# peaks_v30.net
KiCad netlist of a schematic drawn in EAGLE
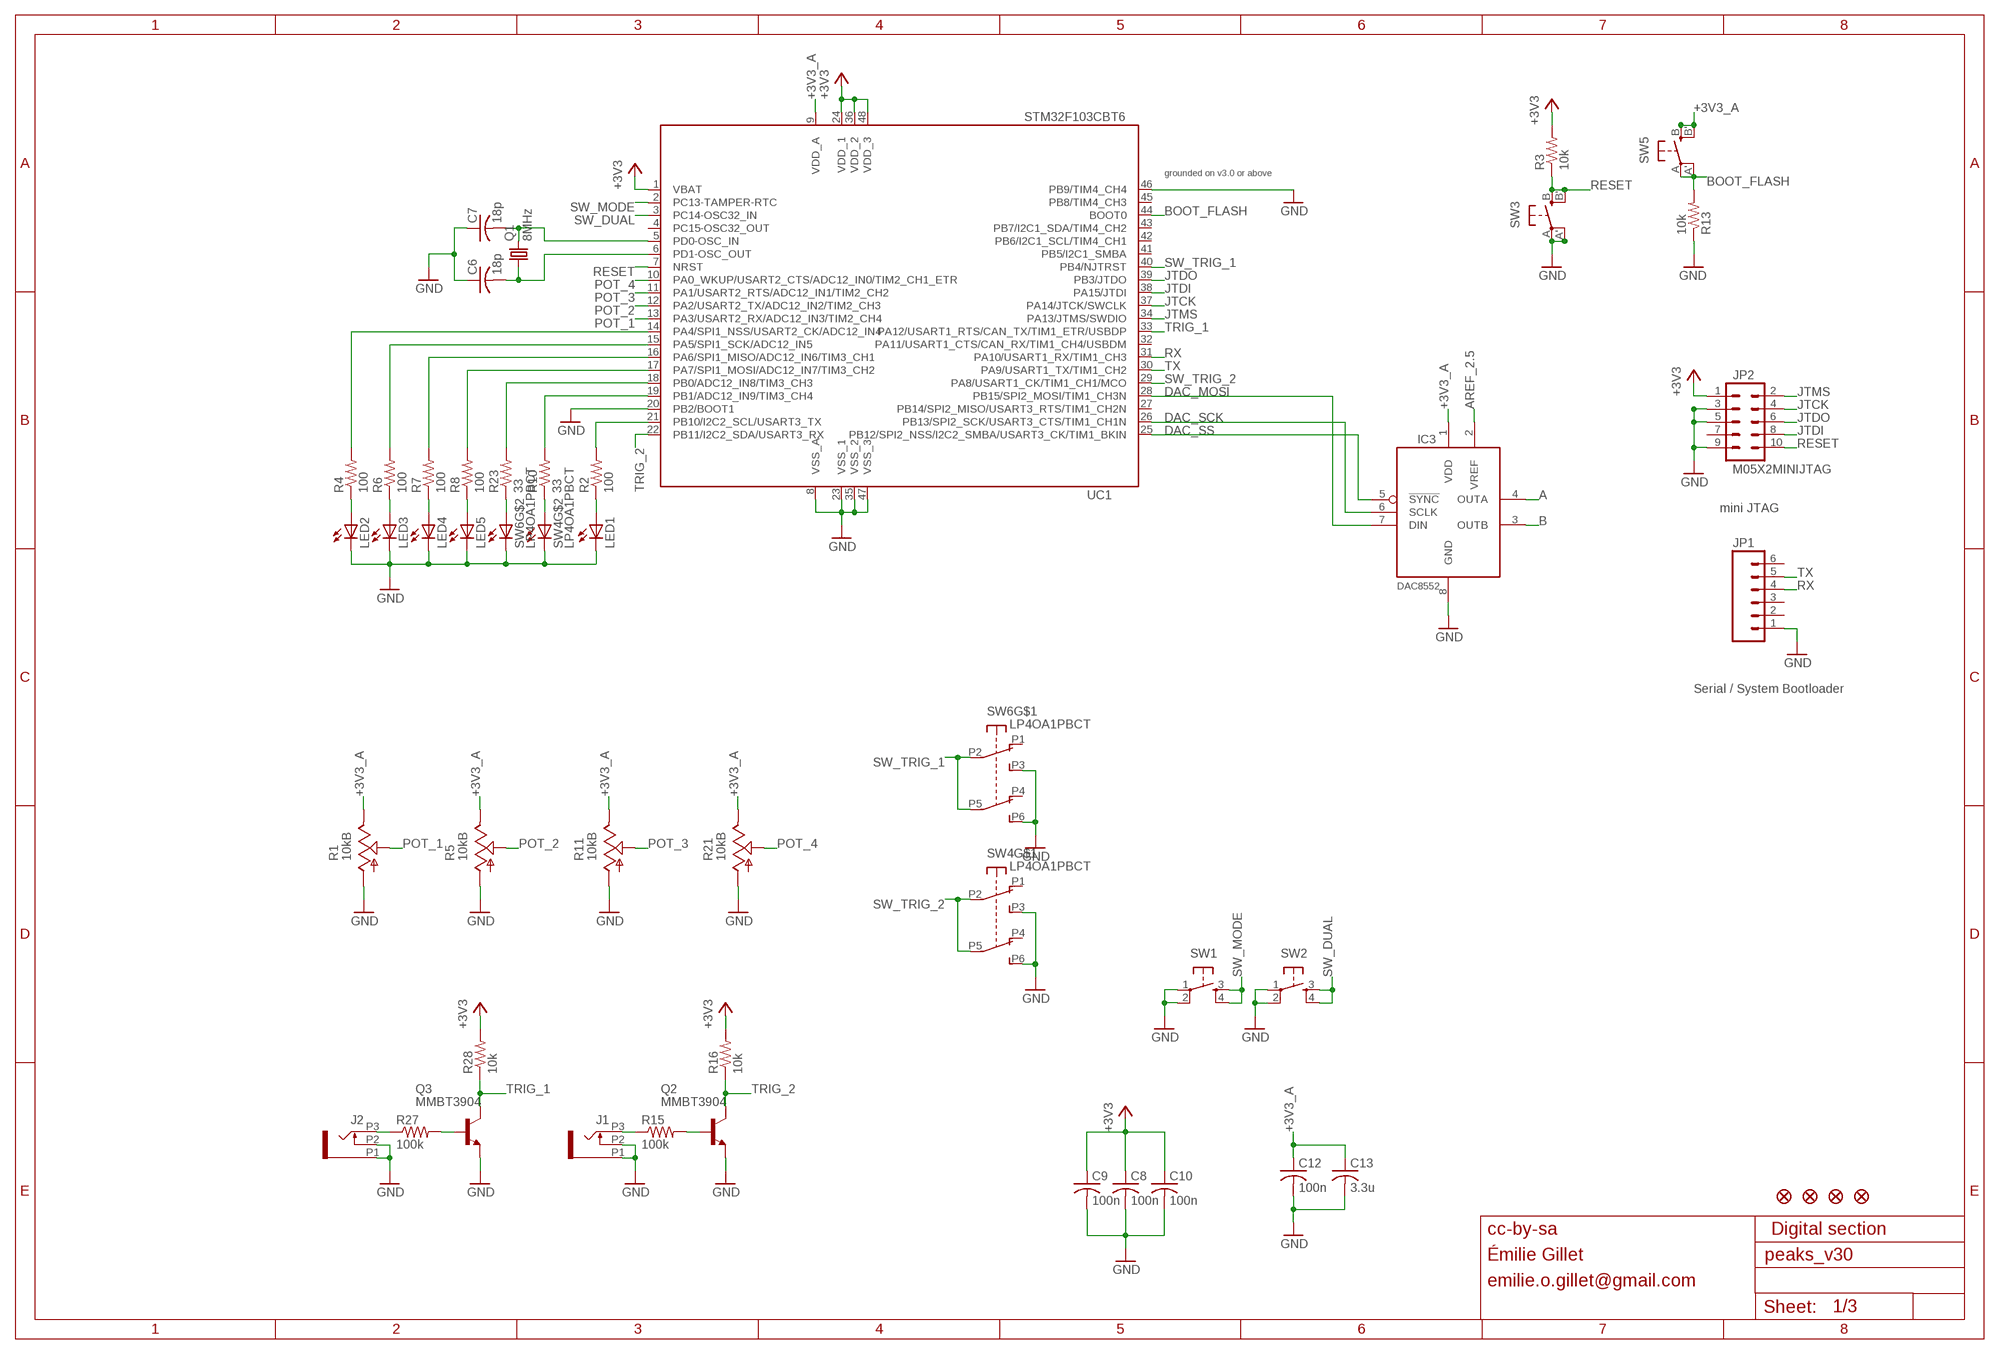
[diagram p0: schematic, sheet 1]
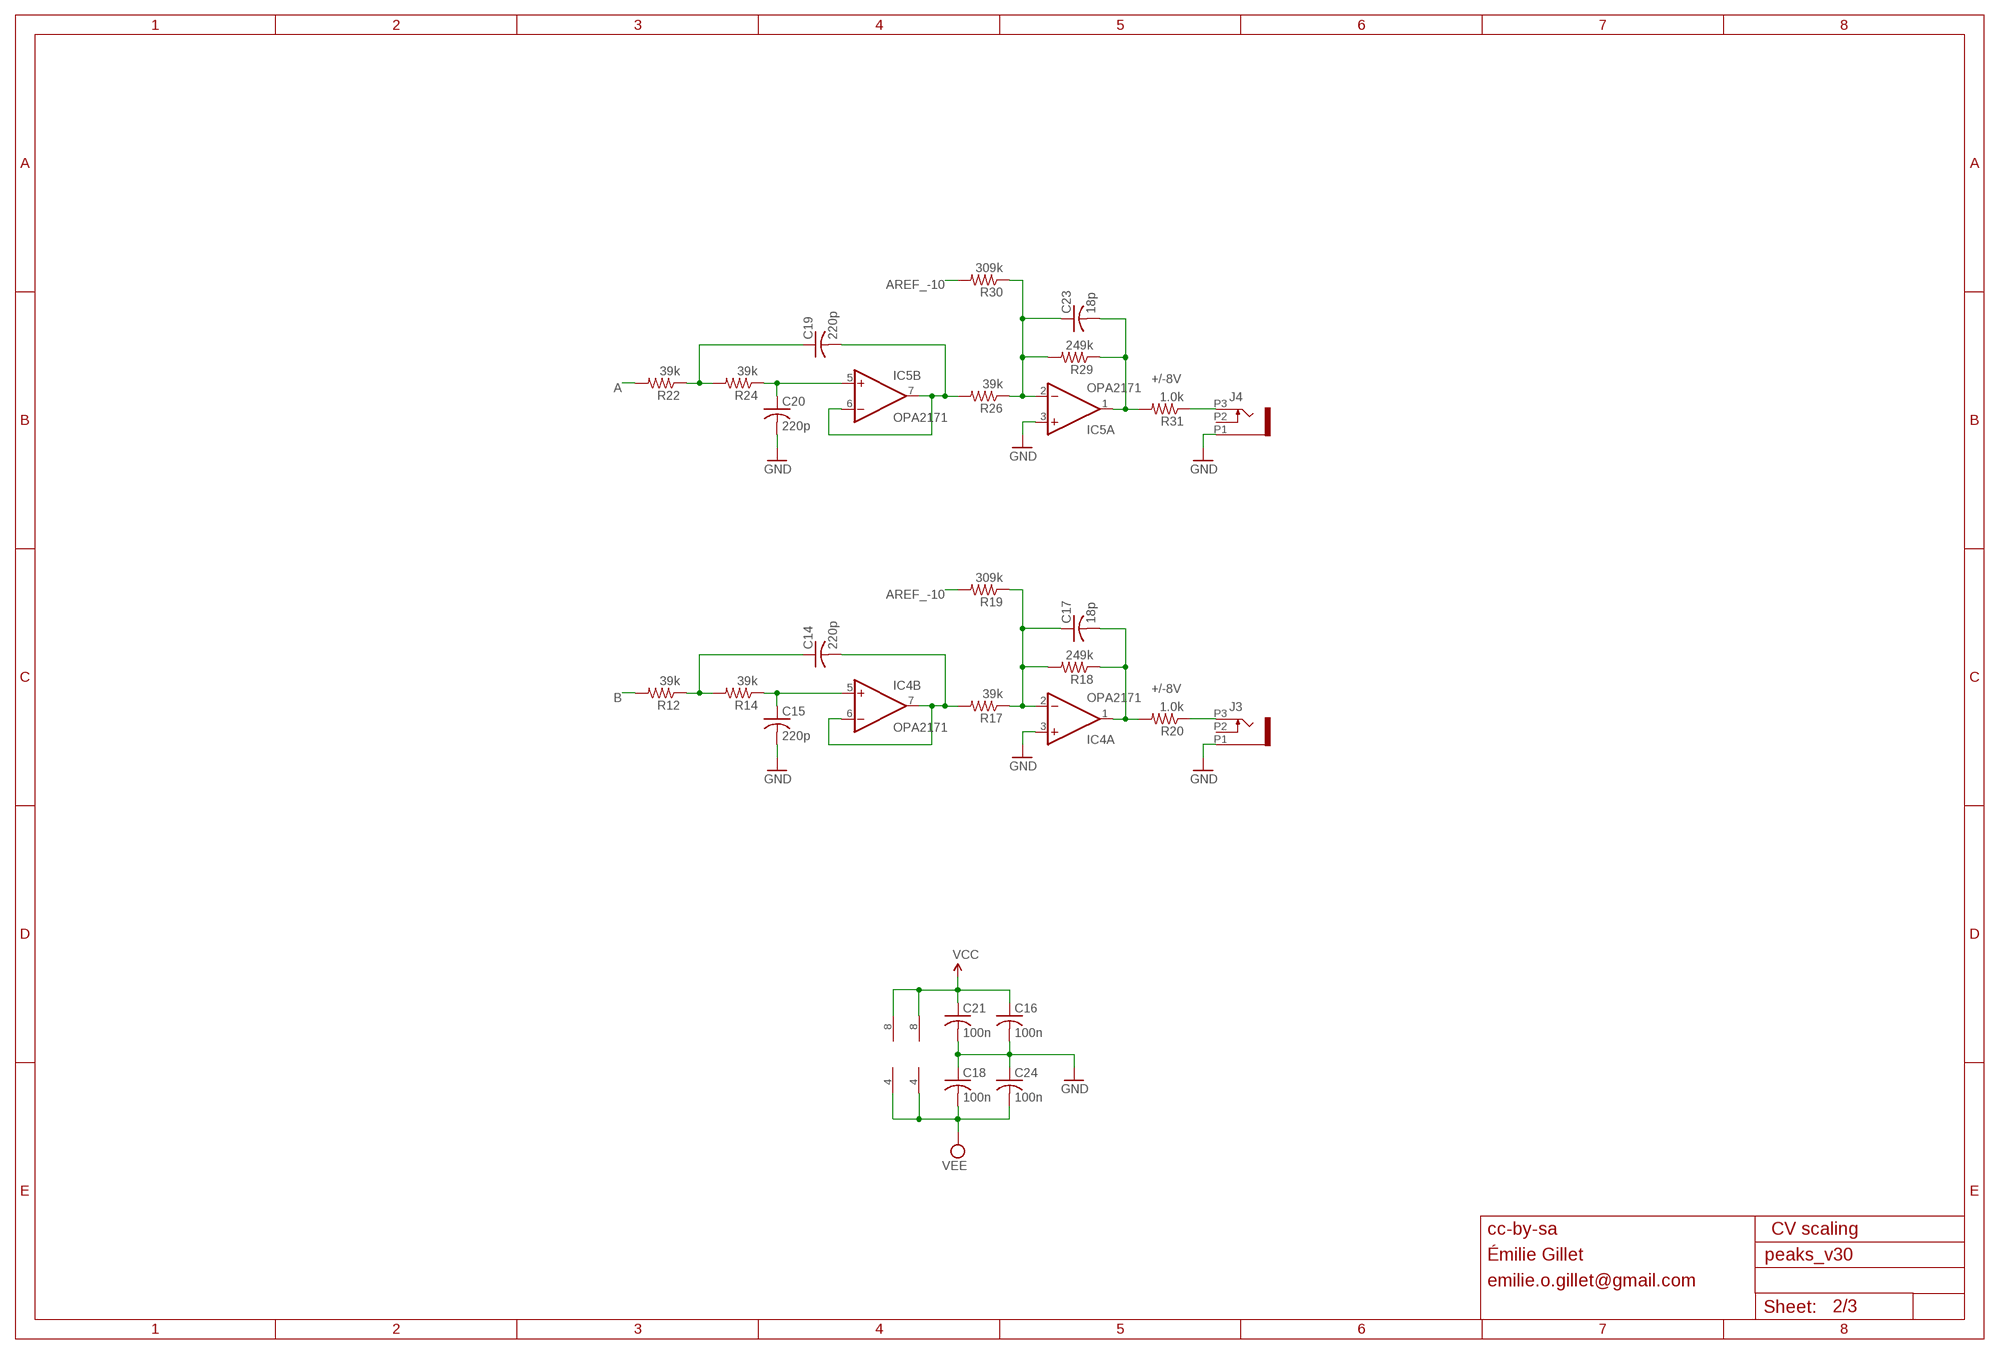
[diagram p1: schematic, sheet 2]
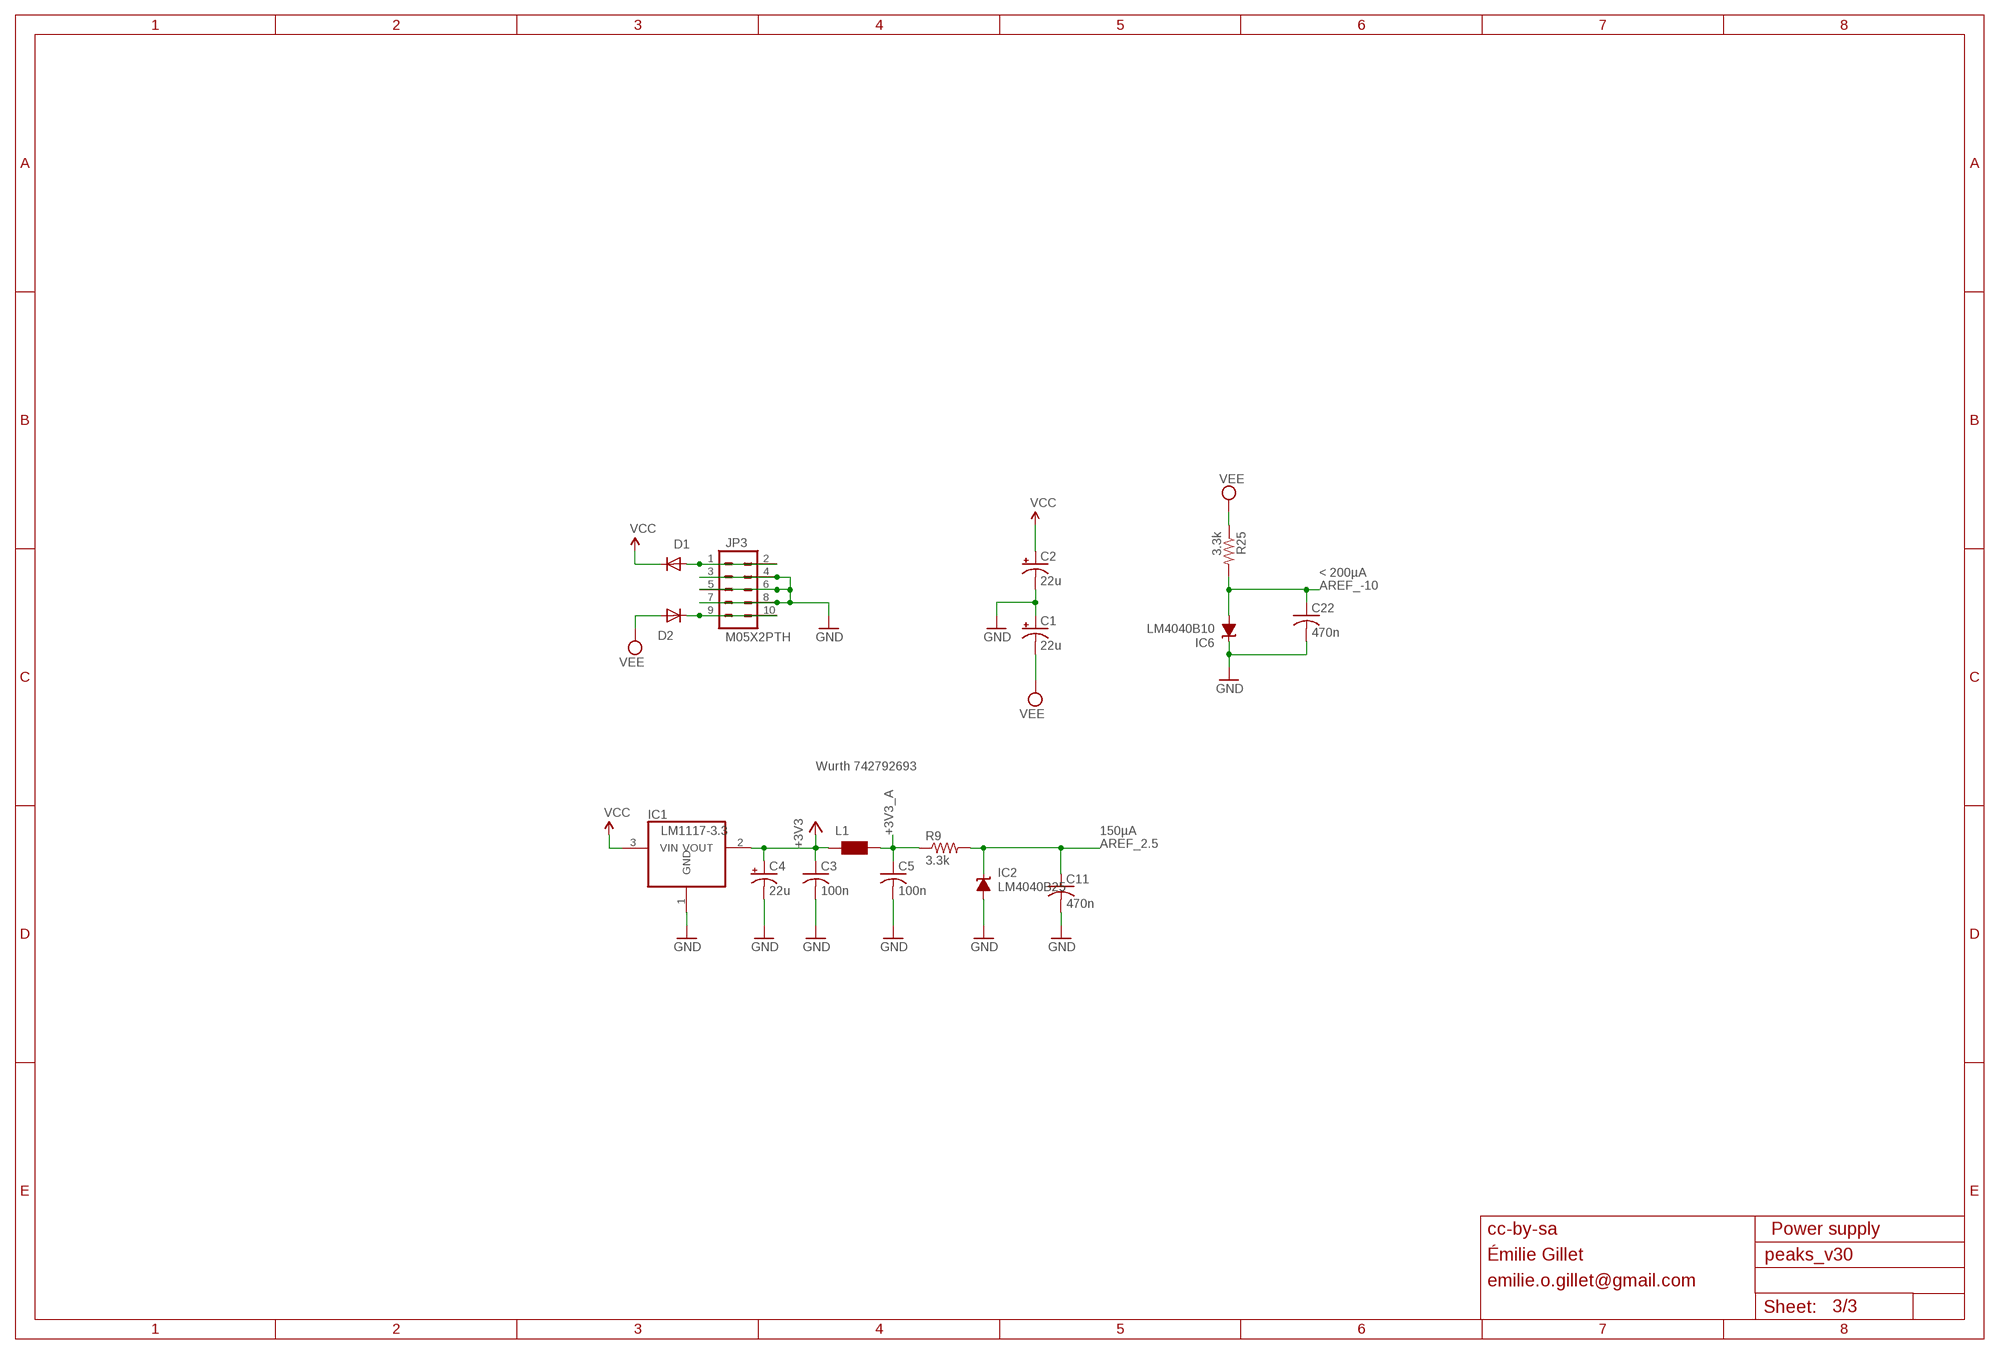
[diagram p2: schematic, sheet 3]

(export (version "E")
  (design (tool "Eeschema 10.0.6"))
  (components
    (comp (ref "C14")
      (value "220p")
      (footprint "eagle-import:C0603")
      (libsource (lib "eagle-import") (part "C-USC0603"))
    )
    (comp (ref "C15")
      (value "220p")
      (footprint "eagle-import:C0603")
      (libsource (lib "eagle-import") (part "C-USC0603"))
    )
    (comp (ref "C16")
      (value "100n")
      (footprint "eagle-import:C0603")
      (libsource (lib "eagle-import") (part "C-USC0603"))
    )
    (comp (ref "C17")
      (value "18p")
      (footprint "eagle-import:C0603")
      (libsource (lib "eagle-import") (part "C-USC0603"))
    )
    (comp (ref "C18")
      (value "100n")
      (footprint "eagle-import:C0603")
      (libsource (lib "eagle-import") (part "C-USC0603"))
    )
    (comp (ref "C19")
      (value "220p")
      (footprint "eagle-import:C0603")
      (libsource (lib "eagle-import") (part "C-USC0603"))
    )
    (comp (ref "C20")
      (value "220p")
      (footprint "eagle-import:C0603")
      (libsource (lib "eagle-import") (part "C-USC0603"))
    )
    (comp (ref "C21")
      (value "100n")
      (footprint "eagle-import:C0603")
      (libsource (lib "eagle-import") (part "C-USC0603"))
    )
    (comp (ref "C23")
      (value "18p")
      (footprint "eagle-import:C0603")
      (libsource (lib "eagle-import") (part "C-USC0603"))
    )
    (comp (ref "C24")
      (value "100n")
      (footprint "eagle-import:C0603")
      (libsource (lib "eagle-import") (part "C-USC0603"))
    )
    (comp (ref "IC4")
      (value "OPA2171")
      (footprint "eagle-import:SO08")
      (libsource (lib "eagle-import") (part "TL072D"))
    )
    (comp (ref "IC5")
      (value "OPA2171")
      (footprint "eagle-import:SO08")
      (libsource (lib "eagle-import") (part "TL072D"))
    )
    (comp (ref "J3")
      (value "PJ301_THONKICONN6")
      (footprint "eagle-import:WQP_PJ_301M6")
      (libsource (lib "eagle-import") (part "PJ301_THONKICONN6"))
    )
    (comp (ref "J4")
      (value "PJ301_THONKICONN6")
      (footprint "eagle-import:WQP_PJ_301M6")
      (libsource (lib "eagle-import") (part "PJ301_THONKICONN6"))
    )
    (comp (ref "R12")
      (value "39k")
      (footprint "eagle-import:R0603")
      (libsource (lib "eagle-import") (part "R-US_R0603"))
    )
    (comp (ref "R14")
      (value "39k")
      (footprint "eagle-import:R0603")
      (libsource (lib "eagle-import") (part "R-US_R0603"))
    )
    (comp (ref "R17")
      (value "39k")
      (footprint "eagle-import:R0603")
      (libsource (lib "eagle-import") (part "R-US_R0603"))
    )
    (comp (ref "R18")
      (value "249k")
      (footprint "eagle-import:R0603")
      (libsource (lib "eagle-import") (part "R-US_R0603"))
    )
    (comp (ref "R19")
      (value "309k")
      (footprint "eagle-import:R0603")
      (libsource (lib "eagle-import") (part "R-US_R0603"))
    )
    (comp (ref "R20")
      (value "1.0k")
      (footprint "eagle-import:R0603")
      (libsource (lib "eagle-import") (part "R-US_R0603"))
    )
    (comp (ref "R22")
      (value "39k")
      (footprint "eagle-import:R0603")
      (libsource (lib "eagle-import") (part "R-US_R0603"))
    )
    (comp (ref "R24")
      (value "39k")
      (footprint "eagle-import:R0603")
      (libsource (lib "eagle-import") (part "R-US_R0603"))
    )
    (comp (ref "R26")
      (value "39k")
      (footprint "eagle-import:R0603")
      (libsource (lib "eagle-import") (part "R-US_R0603"))
    )
    (comp (ref "R29")
      (value "249k")
      (footprint "eagle-import:R0603")
      (libsource (lib "eagle-import") (part "R-US_R0603"))
    )
    (comp (ref "R30")
      (value "309k")
      (footprint "eagle-import:R0603")
      (libsource (lib "eagle-import") (part "R-US_R0603"))
    )
    (comp (ref "R31")
      (value "1.0k")
      (footprint "eagle-import:R0603")
      (libsource (lib "eagle-import") (part "R-US_R0603"))
    )
    (comp (ref "C6")
      (value "18p")
      (footprint "eagle-import:C0603")
      (libsource (lib "eagle-import") (part "C-USC0603"))
    )
    (comp (ref "C7")
      (value "18p")
      (footprint "eagle-import:C0603")
      (libsource (lib "eagle-import") (part "C-USC0603"))
    )
    (comp (ref "C8")
      (value "100n")
      (footprint "eagle-import:C0603")
      (libsource (lib "eagle-import") (part "C-USC0603"))
    )
    (comp (ref "C9")
      (value "100n")
      (footprint "eagle-import:C0603")
      (libsource (lib "eagle-import") (part "C-USC0603"))
    )
    (comp (ref "C10")
      (value "100n")
      (footprint "eagle-import:C0603")
      (libsource (lib "eagle-import") (part "C-USC0603"))
    )
    (comp (ref "C12")
      (value "100n")
      (footprint "eagle-import:C0603")
      (libsource (lib "eagle-import") (part "C-USC0603"))
    )
    (comp (ref "C13")
      (value "3.3u")
      (footprint "eagle-import:C0603")
      (libsource (lib "eagle-import") (part "C-USC0603"))
    )
    (comp (ref "F1")
      (value "FIDUCIAL1X2")
      (footprint "eagle-import:FIDUCIAL-1X2")
      (libsource (lib "eagle-import") (part "FIDUCIAL1X2"))
    )
    (comp (ref "F2")
      (value "FIDUCIAL1X2")
      (footprint "eagle-import:FIDUCIAL-1X2")
      (libsource (lib "eagle-import") (part "FIDUCIAL1X2"))
    )
    (comp (ref "F3")
      (value "FIDUCIAL1X2")
      (footprint "eagle-import:FIDUCIAL-1X2")
      (libsource (lib "eagle-import") (part "FIDUCIAL1X2"))
    )
    (comp (ref "F4")
      (value "FIDUCIAL1X2")
      (footprint "eagle-import:FIDUCIAL-1X2")
      (libsource (lib "eagle-import") (part "FIDUCIAL1X2"))
    )
    (comp (ref "IC3")
      (value "DAC8552")
      (footprint "eagle-import:MSOP-8")
      (libsource (lib "eagle-import") (part "DAC8552"))
    )
    (comp (ref "J1")
      (value "PJ301_THONKICONN6")
      (footprint "eagle-import:WQP_PJ_301M6")
      (libsource (lib "eagle-import") (part "PJ301_THONKICONN6"))
    )
    (comp (ref "J2")
      (value "PJ301_THONKICONN6")
      (footprint "eagle-import:WQP_PJ_301M6")
      (libsource (lib "eagle-import") (part "PJ301_THONKICONN6"))
    )
    (comp (ref "JP1")
      (value "M06SIP")
      (footprint "eagle-import:1X06")
      (libsource (lib "eagle-import") (part "M06SIP"))
    )
    (comp (ref "JP2")
      (value "M05X2MINIJTAG")
      (footprint "eagle-import:2X5-1.27")
      (libsource (lib "eagle-import") (part "M05X2MINIJTAG"))
    )
    (comp (ref "LED1")
      (value "LED3MM")
      (footprint "eagle-import:LED3MM")
      (libsource (lib "eagle-import") (part "LED3MM"))
    )
    (comp (ref "LED2")
      (value "LED3MM")
      (footprint "eagle-import:LED3MM")
      (libsource (lib "eagle-import") (part "LED3MM"))
    )
    (comp (ref "LED3")
      (value "LED3MM")
      (footprint "eagle-import:LED3MM")
      (libsource (lib "eagle-import") (part "LED3MM"))
    )
    (comp (ref "LED4")
      (value "LED3MM")
      (footprint "eagle-import:LED3MM")
      (libsource (lib "eagle-import") (part "LED3MM"))
    )
    (comp (ref "LED5")
      (value "LED3MM")
      (footprint "eagle-import:LED3MM")
      (libsource (lib "eagle-import") (part "LED3MM"))
    )
    (comp (ref "Q1")
      (value "8MHz")
      (footprint "eagle-import:HC49UP")
      (libsource (lib "eagle-import") (part "CRYSTALHC49UP"))
    )
    (comp (ref "Q2")
      (value "MMBT3904")
      (footprint "eagle-import:SOT23-BEC")
      (libsource (lib "eagle-import") (part "-NPN-SOT23-BECMMBT3904LT1"))
    )
    (comp (ref "Q3")
      (value "MMBT3904")
      (footprint "eagle-import:SOT23-BEC")
      (libsource (lib "eagle-import") (part "-NPN-SOT23-BECMMBT3904LT1"))
    )
    (comp (ref "R1")
      (value "10kB")
      (footprint "eagle-import:ALPS_POT_VERTICAL_PS")
      (libsource (lib "eagle-import") (part "POT_USVERTICAL_PS"))
    )
    (comp (ref "R2")
      (value "100")
      (footprint "eagle-import:R0603")
      (libsource (lib "eagle-import") (part "R-US_R0603"))
    )
    (comp (ref "R3")
      (value "10k")
      (footprint "eagle-import:R0603")
      (libsource (lib "eagle-import") (part "R-US_R0603"))
    )
    (comp (ref "R4")
      (value "100")
      (footprint "eagle-import:R0603")
      (libsource (lib "eagle-import") (part "R-US_R0603"))
    )
    (comp (ref "R5")
      (value "10kB")
      (footprint "eagle-import:ALPS_POT_VERTICAL_PS")
      (libsource (lib "eagle-import") (part "POT_USVERTICAL_PS"))
    )
    (comp (ref "R6")
      (value "100")
      (footprint "eagle-import:R0603")
      (libsource (lib "eagle-import") (part "R-US_R0603"))
    )
    (comp (ref "R7")
      (value "100")
      (footprint "eagle-import:R0603")
      (libsource (lib "eagle-import") (part "R-US_R0603"))
    )
    (comp (ref "R8")
      (value "100")
      (footprint "eagle-import:R0603")
      (libsource (lib "eagle-import") (part "R-US_R0603"))
    )
    (comp (ref "R10")
      (value "33")
      (footprint "eagle-import:R0603")
      (libsource (lib "eagle-import") (part "R-US_R0603"))
    )
    (comp (ref "R11")
      (value "10kB")
      (footprint "eagle-import:ALPS_POT_VERTICAL_PS")
      (libsource (lib "eagle-import") (part "POT_USVERTICAL_PS"))
    )
    (comp (ref "R13")
      (value "10k")
      (footprint "eagle-import:R0603")
      (libsource (lib "eagle-import") (part "R-US_R0603"))
    )
    (comp (ref "R15")
      (value "100k")
      (footprint "eagle-import:R0603")
      (libsource (lib "eagle-import") (part "R-US_R0603"))
    )
    (comp (ref "R16")
      (value "10k")
      (footprint "eagle-import:R0603")
      (libsource (lib "eagle-import") (part "R-US_R0603"))
    )
    (comp (ref "R21")
      (value "10kB")
      (footprint "eagle-import:ALPS_POT_VERTICAL_PS")
      (libsource (lib "eagle-import") (part "POT_USVERTICAL_PS"))
    )
    (comp (ref "R23")
      (value "33")
      (footprint "eagle-import:R0603")
      (libsource (lib "eagle-import") (part "R-US_R0603"))
    )
    (comp (ref "R27")
      (value "100k")
      (footprint "eagle-import:R0603")
      (libsource (lib "eagle-import") (part "R-US_R0603"))
    )
    (comp (ref "R28")
      (value "10k")
      (footprint "eagle-import:R0603")
      (libsource (lib "eagle-import") (part "R-US_R0603"))
    )
    (comp (ref "SW1")
      (value "TAC_SWITCHPTH")
      (footprint "eagle-import:TACTILE-PTH")
      (libsource (lib "eagle-import") (part "TAC_SWITCHPTH"))
    )
    (comp (ref "SW2")
      (value "TAC_SWITCHPTH")
      (footprint "eagle-import:TACTILE-PTH")
      (libsource (lib "eagle-import") (part "TAC_SWITCHPTH"))
    )
    (comp (ref "SW3")
      (value "EVQQ2")
      (footprint "eagle-import:EVQ-Q2")
      (libsource (lib "eagle-import") (part "EVQQ2"))
    )
    (comp (ref "SW4")
      (value "LP4OA1PBCT")
      (footprint "eagle-import:LP4OA1PBCT")
      (libsource (lib "eagle-import") (part "LP4OA1PBCT"))
    )
    (comp (ref "SW5")
      (value "EVQQ2")
      (footprint "eagle-import:EVQ-Q2")
      (libsource (lib "eagle-import") (part "EVQQ2"))
    )
    (comp (ref "SW6")
      (value "LP4OA1PBCT")
      (footprint "eagle-import:LP4OA1PBCT")
      (libsource (lib "eagle-import") (part "LP4OA1PBCT"))
    )
    (comp (ref "UC1")
      (value "STM32F103CBT6")
      (footprint "eagle-import:LQFP48")
      (libsource (lib "eagle-import") (part "STM32F103CB"))
    )
    (comp (ref "C1")
      (value "22u")
      (footprint "eagle-import:PANASONIC_C")
      (libsource (lib "eagle-import") (part "CPOL-USC"))
    )
    (comp (ref "C2")
      (value "22u")
      (footprint "eagle-import:PANASONIC_C")
      (libsource (lib "eagle-import") (part "CPOL-USC"))
    )
    (comp (ref "C3")
      (value "100n")
      (footprint "eagle-import:C0603")
      (libsource (lib "eagle-import") (part "C-USC0603"))
    )
    (comp (ref "C4")
      (value "22u")
      (footprint "eagle-import:PANASONIC_C")
      (libsource (lib "eagle-import") (part "CPOL-USC"))
    )
    (comp (ref "C5")
      (value "100n")
      (footprint "eagle-import:C0603")
      (libsource (lib "eagle-import") (part "C-USC0603"))
    )
    (comp (ref "C11")
      (value "470n")
      (footprint "eagle-import:C0603")
      (libsource (lib "eagle-import") (part "C-USC0603"))
    )
    (comp (ref "C22")
      (value "470n")
      (footprint "eagle-import:C0603")
      (libsource (lib "eagle-import") (part "C-USC0603"))
    )
    (comp (ref "D1")
      (value "1N5819HW")
      (footprint "eagle-import:SOD123")
      (libsource (lib "eagle-import") (part "DIODE-SOD123"))
    )
    (comp (ref "D2")
      (value "1N5819HW")
      (footprint "eagle-import:SOD123")
      (libsource (lib "eagle-import") (part "DIODE-SOD123"))
    )
    (comp (ref "IC1")
      (value "LM1117-3.3")
      (footprint "eagle-import:SOT223")
      (libsource (lib "eagle-import") (part "REG1117"))
    )
    (comp (ref "IC2")
      (value "LM4040B25")
      (footprint "eagle-import:DBZ_R-PDSO-G3")
      (libsource (lib "eagle-import") (part "LM4041DBZB12"))
    )
    (comp (ref "IC6")
      (value "LM4040B10")
      (footprint "eagle-import:DBZ_R-PDSO-G3")
      (libsource (lib "eagle-import") (part "LM4041DBZB12"))
    )
    (comp (ref "JP3")
      (value "M05X2PTH")
      (footprint "eagle-import:AVR_ICSP")
      (libsource (lib "eagle-import") (part "M05X2PTH"))
    )
    (comp (ref "L1")
      (value "WE-CBF_0603")
      (footprint "eagle-import:0603")
      (libsource (lib "eagle-import") (part "WE-CBF_0603"))
    )
    (comp (ref "R9")
      (value "3.3k")
      (footprint "eagle-import:R0603")
      (libsource (lib "eagle-import") (part "R-US_R0603"))
    )
    (comp (ref "R25")
      (value "3.3k")
      (footprint "eagle-import:R0603")
      (libsource (lib "eagle-import") (part "R-US_R0603"))
    )
  )
  (nets
    (net (code "1") (name "+3V3") (class "Default")
      (node (ref "C10") (pin "1") (pinfunction "1_1") (pintype "passive"))
      (node (ref "C3") (pin "1") (pinfunction "1_1") (pintype "passive"))
      (node (ref "C4") (pin "+") (pinfunction "+_+") (pintype "passive"))
      (node (ref "C8") (pin "1") (pinfunction "1_1") (pintype "passive"))
      (node (ref "C9") (pin "1") (pinfunction "1_1") (pintype "passive"))
      (node (ref "IC1") (pin "2") (pinfunction "VOUT_2") (pintype "output"))
      (node (ref "JP2") (pin "1") (pinfunction "1_1") (pintype "passive"))
      (node (ref "L1") (pin "1") (pinfunction "1_1") (pintype "passive"))
      (node (ref "R16") (pin "2") (pinfunction "2_2") (pintype "passive"))
      (node (ref "R28") (pin "2") (pinfunction "2_2") (pintype "passive"))
      (node (ref "R3") (pin "2") (pinfunction "2_2") (pintype "passive"))
      (node (ref "UC1") (pin "1") (pinfunction "VBAT_1") (pintype "power_in"))
      (node (ref "UC1") (pin "24") (pinfunction "VDD_1_24") (pintype "power_in"))
      (node (ref "UC1") (pin "36") (pinfunction "VDD_2_36") (pintype "power_in"))
      (node (ref "UC1") (pin "48") (pinfunction "VDD_3_48") (pintype "power_in"))
    )
    (net (code "2") (name "+3V3_A") (class "Default")
      (node (ref "C12") (pin "1") (pinfunction "1_1") (pintype "passive"))
      (node (ref "C13") (pin "1") (pinfunction "1_1") (pintype "passive"))
      (node (ref "C5") (pin "1") (pinfunction "1_1") (pintype "passive"))
      (node (ref "IC3") (pin "1") (pinfunction "VDD_1") (pintype "power_in"))
      (node (ref "L1") (pin "2") (pinfunction "2_2") (pintype "passive"))
      (node (ref "R1") (pin "P$1") (pinfunction "E_P$1") (pintype "passive"))
      (node (ref "R11") (pin "P$1") (pinfunction "E_P$1") (pintype "passive"))
      (node (ref "R21") (pin "P$1") (pinfunction "E_P$1") (pintype "passive"))
      (node (ref "R5") (pin "P$1") (pinfunction "E_P$1") (pintype "passive"))
      (node (ref "R9") (pin "1") (pinfunction "1_1") (pintype "passive"))
      (node (ref "SW5") (pin "B") (pinfunction "S_B") (pintype "passive"))
      (node (ref "SW5") (pin "B'") (pinfunction "S1_B'") (pintype "passive"))
      (node (ref "UC1") (pin "9") (pinfunction "VDD_A_9") (pintype "power_in"))
    )
    (net (code "3") (name "A") (class "Default")
      (node (ref "IC3") (pin "4") (pinfunction "OUTA_4") (pintype "output"))
      (node (ref "R22") (pin "2") (pinfunction "2_2") (pintype "passive"))
    )
    (net (code "4") (name "AREF_-10") (class "Default")
      (node (ref "C22") (pin "1") (pinfunction "1_1") (pintype "passive"))
      (node (ref "IC6") (pin "2") (pinfunction "A_2") (pintype "passive"))
      (node (ref "R19") (pin "2") (pinfunction "2_2") (pintype "passive"))
      (node (ref "R25") (pin "2") (pinfunction "2_2") (pintype "passive"))
      (node (ref "R30") (pin "2") (pinfunction "2_2") (pintype "passive"))
    )
    (net (code "5") (name "AREF_2.5") (class "Default")
      (node (ref "C11") (pin "1") (pinfunction "1_1") (pintype "passive"))
      (node (ref "IC2") (pin "1") (pinfunction "C_1") (pintype "passive"))
      (node (ref "IC3") (pin "2") (pinfunction "VREF_2") (pintype "power_in"))
      (node (ref "R9") (pin "2") (pinfunction "2_2") (pintype "passive"))
    )
    (net (code "6") (name "B") (class "Default")
      (node (ref "IC3") (pin "3") (pinfunction "OUTB_3") (pintype "input"))
      (node (ref "R12") (pin "2") (pinfunction "2_2") (pintype "passive"))
    )
    (net (code "7") (name "BOOT_FLASH") (class "Default")
      (node (ref "R13") (pin "2") (pinfunction "2_2") (pintype "passive"))
      (node (ref "SW5") (pin "A") (pinfunction "P_A") (pintype "passive"))
      (node (ref "SW5") (pin "A'") (pinfunction "P1_A'") (pintype "passive"))
      (node (ref "UC1") (pin "44") (pinfunction "BOOT0_44") (pintype "input"))
    )
    (net (code "8") (name "DAC_MOSI") (class "Default")
      (node (ref "IC3") (pin "7") (pinfunction "DIN_7") (pintype "bidirectional"))
      (node (ref "UC1") (pin "28") (pinfunction "PB15/SPI2_MOSI/TIM1_CH3N_28") (pintype "input"))
    )
    (net (code "9") (name "DAC_SCK") (class "Default")
      (node (ref "IC3") (pin "6") (pinfunction "SCLK_6") (pintype "bidirectional"))
      (node (ref "UC1") (pin "26") (pinfunction "PB13/SPI2_SCK/USART3_CTS/TIM1_CH1N_26") (pintype "input"))
    )
    (net (code "10") (name "DAC_SS") (class "Default")
      (node (ref "IC3") (pin "5") (pinfunction "~{SYNC}_5") (pintype "bidirectional"))
      (node (ref "UC1") (pin "25") (pinfunction "PB12/SPI2_NSS/I2C2_SMBA/USART3_CK/TIM1_BKIN_25") (pintype "input"))
    )
    (net (code "11") (name "GND") (class "Default")
      (node (ref "C1") (pin "+") (pinfunction "+_+") (pintype "passive"))
      (node (ref "C10") (pin "2") (pinfunction "2_2") (pintype "passive"))
      (node (ref "C11") (pin "2") (pinfunction "2_2") (pintype "passive"))
      (node (ref "C12") (pin "2") (pinfunction "2_2") (pintype "passive"))
      (node (ref "C13") (pin "2") (pinfunction "2_2") (pintype "passive"))
      (node (ref "C15") (pin "2") (pinfunction "2_2") (pintype "passive"))
      (node (ref "C16") (pin "2") (pinfunction "2_2") (pintype "passive"))
      (node (ref "C18") (pin "1") (pinfunction "1_1") (pintype "passive"))
      (node (ref "C2") (pin "-") (pinfunction "-_-") (pintype "passive"))
      (node (ref "C20") (pin "2") (pinfunction "2_2") (pintype "passive"))
      (node (ref "C21") (pin "2") (pinfunction "2_2") (pintype "passive"))
      (node (ref "C22") (pin "2") (pinfunction "2_2") (pintype "passive"))
      (node (ref "C24") (pin "1") (pinfunction "1_1") (pintype "passive"))
      (node (ref "C3") (pin "2") (pinfunction "2_2") (pintype "passive"))
      (node (ref "C4") (pin "-") (pinfunction "-_-") (pintype "passive"))
      (node (ref "C5") (pin "2") (pinfunction "2_2") (pintype "passive"))
      (node (ref "C6") (pin "1") (pinfunction "1_1") (pintype "passive"))
      (node (ref "C7") (pin "1") (pinfunction "1_1") (pintype "passive"))
      (node (ref "C8") (pin "2") (pinfunction "2_2") (pintype "passive"))
      (node (ref "C9") (pin "2") (pinfunction "2_2") (pintype "passive"))
      (node (ref "IC1") (pin "1") (pinfunction "GND_1") (pintype "power_in"))
      (node (ref "IC2") (pin "2") (pinfunction "A_2") (pintype "passive"))
      (node (ref "IC3") (pin "8") (pinfunction "GND_8") (pintype "power_in"))
      (node (ref "IC4") (pin "3") (pinfunction "+IN_3") (pintype "input"))
      (node (ref "IC5") (pin "3") (pinfunction "+IN_3") (pintype "input"))
      (node (ref "IC6") (pin "1") (pinfunction "C_1") (pintype "passive"))
      (node (ref "J1") (pin "P1") (pinfunction "1_P1") (pintype "passive"))
      (node (ref "J1") (pin "P2") (pinfunction "2_P2") (pintype "passive"))
      (node (ref "J2") (pin "P1") (pinfunction "1_P1") (pintype "passive"))
      (node (ref "J2") (pin "P2") (pinfunction "2_P2") (pintype "passive"))
      (node (ref "J3") (pin "P1") (pinfunction "1_P1") (pintype "passive"))
      (node (ref "J4") (pin "P1") (pinfunction "1_P1") (pintype "passive"))
      (node (ref "JP1") (pin "1") (pinfunction "1_1") (pintype "passive"))
      (node (ref "JP2") (pin "3") (pinfunction "3_3") (pintype "passive"))
      (node (ref "JP2") (pin "5") (pinfunction "5_5") (pintype "passive"))
      (node (ref "JP2") (pin "9") (pinfunction "9_9") (pintype "passive"))
      (node (ref "JP3") (pin "3") (pinfunction "3_3") (pintype "passive"))
      (node (ref "JP3") (pin "4") (pinfunction "4_4") (pintype "passive"))
      (node (ref "JP3") (pin "5") (pinfunction "5_5") (pintype "passive"))
      (node (ref "JP3") (pin "6") (pinfunction "6_6") (pintype "passive"))
      (node (ref "JP3") (pin "7") (pinfunction "7_7") (pintype "passive"))
      (node (ref "JP3") (pin "8") (pinfunction "8_8") (pintype "passive"))
      (node (ref "LED1") (pin "K") (pinfunction "C_K") (pintype "passive"))
      (node (ref "LED2") (pin "K") (pinfunction "C_K") (pintype "passive"))
      (node (ref "LED3") (pin "K") (pinfunction "C_K") (pintype "passive"))
      (node (ref "LED4") (pin "K") (pinfunction "C_K") (pintype "passive"))
      (node (ref "LED5") (pin "K") (pinfunction "C_K") (pintype "passive"))
      (node (ref "Q2") (pin "E") (pinfunction "E_E") (pintype "passive"))
      (node (ref "Q3") (pin "E") (pinfunction "E_E") (pintype "passive"))
      (node (ref "R1") (pin "P$3") (pinfunction "A_P$3") (pintype "passive"))
      (node (ref "R11") (pin "P$3") (pinfunction "A_P$3") (pintype "passive"))
      (node (ref "R13") (pin "1") (pinfunction "1_1") (pintype "passive"))
      (node (ref "R21") (pin "P$3") (pinfunction "A_P$3") (pintype "passive"))
      (node (ref "R5") (pin "P$3") (pinfunction "A_P$3") (pintype "passive"))
      (node (ref "SW1") (pin "1") (pinfunction "1_1") (pintype "passive"))
      (node (ref "SW1") (pin "2") (pinfunction "2_2") (pintype "passive"))
      (node (ref "SW2") (pin "1") (pinfunction "1_1") (pintype "passive"))
      (node (ref "SW2") (pin "2") (pinfunction "2_2") (pintype "passive"))
      (node (ref "SW3") (pin "A") (pinfunction "P_A") (pintype "passive"))
      (node (ref "SW3") (pin "A'") (pinfunction "P1_A'") (pintype "passive"))
      (node (ref "SW4") (pin "L2") (pinfunction "L2_L2") (pintype "passive"))
      (node (ref "SW4") (pin "P3") (pinfunction "A3_P3") (pintype "passive"))
      (node (ref "SW4") (pin "P6") (pinfunction "B3_P6") (pintype "passive"))
      (node (ref "SW6") (pin "L2") (pinfunction "L2_L2") (pintype "passive"))
      (node (ref "SW6") (pin "P3") (pinfunction "A3_P3") (pintype "passive"))
      (node (ref "SW6") (pin "P6") (pinfunction "B3_P6") (pintype "passive"))
      (node (ref "UC1") (pin "20") (pinfunction "PB2/BOOT1_20") (pintype "bidirectional"))
      (node (ref "UC1") (pin "23") (pinfunction "VSS_1_23") (pintype "power_in"))
      (node (ref "UC1") (pin "35") (pinfunction "VSS_2_35") (pintype "power_in"))
      (node (ref "UC1") (pin "46") (pinfunction "PB9/TIM4_CH4_46") (pintype "input"))
      (node (ref "UC1") (pin "47") (pinfunction "VSS_3_47") (pintype "power_in"))
      (node (ref "UC1") (pin "8") (pinfunction "VSS_A_8") (pintype "power_in"))
    )
    (net (code "12") (name "JTCK") (class "Default")
      (node (ref "JP2") (pin "4") (pinfunction "4_4") (pintype "passive"))
      (node (ref "UC1") (pin "37") (pinfunction "PA14/JTCK/SWCLK_37") (pintype "bidirectional"))
    )
    (net (code "13") (name "JTDI") (class "Default")
      (node (ref "JP2") (pin "8") (pinfunction "8_8") (pintype "passive"))
      (node (ref "UC1") (pin "38") (pinfunction "PA15/JTDI_38") (pintype "bidirectional"))
    )
    (net (code "14") (name "JTDO") (class "Default")
      (node (ref "JP2") (pin "6") (pinfunction "6_6") (pintype "passive"))
      (node (ref "UC1") (pin "39") (pinfunction "PB3/JTDO_39") (pintype "bidirectional"))
    )
    (net (code "15") (name "JTMS") (class "Default")
      (node (ref "JP2") (pin "2") (pinfunction "2_2") (pintype "passive"))
      (node (ref "UC1") (pin "34") (pinfunction "PA13/JTMS/SWDIO_34") (pintype "bidirectional"))
    )
    (net (code "16") (name "Net-(C14-Pad1)") (class "Default")
      (node (ref "C14") (pin "1") (pinfunction "1_1") (pintype "passive"))
      (node (ref "R12") (pin "1") (pinfunction "1_1") (pintype "passive"))
      (node (ref "R14") (pin "2") (pinfunction "2_2") (pintype "passive"))
    )
    (net (code "17") (name "Net-(C19-Pad1)") (class "Default")
      (node (ref "C19") (pin "1") (pinfunction "1_1") (pintype "passive"))
      (node (ref "R22") (pin "1") (pinfunction "1_1") (pintype "passive"))
      (node (ref "R24") (pin "2") (pinfunction "2_2") (pintype "passive"))
    )
    (net (code "18") (name "Net-(D1-PadA)") (class "Default")
      (node (ref "D1") (pin "A") (pinfunction "A_A") (pintype "passive"))
      (node (ref "JP3") (pin "1") (pinfunction "1_1") (pintype "passive"))
      (node (ref "JP3") (pin "2") (pinfunction "2_2") (pintype "passive"))
    )
    (net (code "19") (name "Net-(D2-PadC)") (class "Default")
      (node (ref "D2") (pin "C") (pinfunction "C_C") (pintype "passive"))
      (node (ref "JP3") (pin "10") (pinfunction "10_10") (pintype "passive"))
      (node (ref "JP3") (pin "9") (pinfunction "9_9") (pintype "passive"))
    )
    (net (code "20") (name "Net-(IC4A--IN)") (class "Default")
      (node (ref "C17") (pin "1") (pinfunction "1_1") (pintype "passive"))
      (node (ref "IC4") (pin "2") (pinfunction "-IN_2") (pintype "input"))
      (node (ref "R17") (pin "1") (pinfunction "1_1") (pintype "passive"))
      (node (ref "R18") (pin "2") (pinfunction "2_2") (pintype "passive"))
      (node (ref "R19") (pin "1") (pinfunction "1_1") (pintype "passive"))
    )
    (net (code "21") (name "Net-(IC4A-OUT)") (class "Default")
      (node (ref "C17") (pin "2") (pinfunction "2_2") (pintype "passive"))
      (node (ref "IC4") (pin "1") (pinfunction "OUT_1") (pintype "output"))
      (node (ref "R18") (pin "1") (pinfunction "1_1") (pintype "passive"))
      (node (ref "R20") (pin "2") (pinfunction "2_2") (pintype "passive"))
    )
    (net (code "22") (name "Net-(IC4B-+IN)") (class "Default")
      (node (ref "C15") (pin "1") (pinfunction "1_1") (pintype "passive"))
      (node (ref "IC4") (pin "5") (pinfunction "+IN_5") (pintype "input"))
      (node (ref "R14") (pin "1") (pinfunction "1_1") (pintype "passive"))
    )
    (net (code "23") (name "Net-(IC4B--IN)") (class "Default")
      (node (ref "C14") (pin "2") (pinfunction "2_2") (pintype "passive"))
      (node (ref "IC4") (pin "6") (pinfunction "-IN_6") (pintype "input"))
      (node (ref "IC4") (pin "7") (pinfunction "OUT_7") (pintype "output"))
      (node (ref "R17") (pin "2") (pinfunction "2_2") (pintype "passive"))
    )
    (net (code "24") (name "Net-(IC5A--IN)") (class "Default")
      (node (ref "C23") (pin "1") (pinfunction "1_1") (pintype "passive"))
      (node (ref "IC5") (pin "2") (pinfunction "-IN_2") (pintype "input"))
      (node (ref "R26") (pin "1") (pinfunction "1_1") (pintype "passive"))
      (node (ref "R29") (pin "2") (pinfunction "2_2") (pintype "passive"))
      (node (ref "R30") (pin "1") (pinfunction "1_1") (pintype "passive"))
    )
    (net (code "25") (name "Net-(IC5A-OUT)") (class "Default")
      (node (ref "C23") (pin "2") (pinfunction "2_2") (pintype "passive"))
      (node (ref "IC5") (pin "1") (pinfunction "OUT_1") (pintype "output"))
      (node (ref "R29") (pin "1") (pinfunction "1_1") (pintype "passive"))
      (node (ref "R31") (pin "2") (pinfunction "2_2") (pintype "passive"))
    )
    (net (code "26") (name "Net-(IC5B-+IN)") (class "Default")
      (node (ref "C20") (pin "1") (pinfunction "1_1") (pintype "passive"))
      (node (ref "IC5") (pin "5") (pinfunction "+IN_5") (pintype "input"))
      (node (ref "R24") (pin "1") (pinfunction "1_1") (pintype "passive"))
    )
    (net (code "27") (name "Net-(IC5B--IN)") (class "Default")
      (node (ref "C19") (pin "2") (pinfunction "2_2") (pintype "passive"))
      (node (ref "IC5") (pin "6") (pinfunction "-IN_6") (pintype "input"))
      (node (ref "IC5") (pin "7") (pinfunction "OUT_7") (pintype "output"))
      (node (ref "R26") (pin "2") (pinfunction "2_2") (pintype "passive"))
    )
    (net (code "28") (name "Net-(J1-3)") (class "Default")
      (node (ref "J1") (pin "P3") (pinfunction "3_P3") (pintype "passive"))
      (node (ref "R15") (pin "1") (pinfunction "1_1") (pintype "passive"))
    )
    (net (code "29") (name "Net-(J2-3)") (class "Default")
      (node (ref "J2") (pin "P3") (pinfunction "3_P3") (pintype "passive"))
      (node (ref "R27") (pin "1") (pinfunction "1_1") (pintype "passive"))
    )
    (net (code "30") (name "Net-(J3-3)") (class "Default")
      (node (ref "J3") (pin "P3") (pinfunction "3_P3") (pintype "passive"))
      (node (ref "R20") (pin "1") (pinfunction "1_1") (pintype "passive"))
    )
    (net (code "31") (name "Net-(J4-3)") (class "Default")
      (node (ref "J4") (pin "P3") (pinfunction "3_P3") (pintype "passive"))
      (node (ref "R31") (pin "1") (pinfunction "1_1") (pintype "passive"))
    )
    (net (code "32") (name "Net-(LED1-PadA)") (class "Default")
      (node (ref "LED1") (pin "A") (pinfunction "A_A") (pintype "passive"))
      (node (ref "R2") (pin "1") (pinfunction "1_1") (pintype "passive"))
    )
    (net (code "33") (name "Net-(LED2-PadA)") (class "Default")
      (node (ref "LED2") (pin "A") (pinfunction "A_A") (pintype "passive"))
      (node (ref "R4") (pin "1") (pinfunction "1_1") (pintype "passive"))
    )
    (net (code "34") (name "Net-(LED3-PadA)") (class "Default")
      (node (ref "LED3") (pin "A") (pinfunction "A_A") (pintype "passive"))
      (node (ref "R6") (pin "1") (pinfunction "1_1") (pintype "passive"))
    )
    (net (code "35") (name "Net-(LED4-PadA)") (class "Default")
      (node (ref "LED4") (pin "A") (pinfunction "A_A") (pintype "passive"))
      (node (ref "R7") (pin "1") (pinfunction "1_1") (pintype "passive"))
    )
    (net (code "36") (name "Net-(LED5-PadA)") (class "Default")
      (node (ref "LED5") (pin "A") (pinfunction "A_A") (pintype "passive"))
      (node (ref "R8") (pin "1") (pinfunction "1_1") (pintype "passive"))
    )
    (net (code "37") (name "Net-(Q2-PadB)") (class "Default")
      (node (ref "Q2") (pin "B") (pinfunction "B_B") (pintype "passive"))
      (node (ref "R15") (pin "2") (pinfunction "2_2") (pintype "passive"))
    )
    (net (code "38") (name "Net-(Q3-PadB)") (class "Default")
      (node (ref "Q3") (pin "B") (pinfunction "B_B") (pintype "passive"))
      (node (ref "R27") (pin "2") (pinfunction "2_2") (pintype "passive"))
    )
    (net (code "39") (name "Net-(R10-Pad1)") (class "Default")
      (node (ref "R10") (pin "1") (pinfunction "1_1") (pintype "passive"))
      (node (ref "SW4") (pin "L1") (pinfunction "L1_L1") (pintype "passive"))
    )
    (net (code "40") (name "Net-(R23-Pad1)") (class "Default")
      (node (ref "R23") (pin "1") (pinfunction "1_1") (pintype "passive"))
      (node (ref "SW6") (pin "L1") (pinfunction "L1_L1") (pintype "passive"))
    )
    (net (code "41") (name "Net-(UC1-PA4{slash}SPI1_NSS{slash}USART2_CK{slash}ADC12_IN4)") (class "Default")
      (node (ref "R4") (pin "2") (pinfunction "2_2") (pintype "passive"))
      (node (ref "UC1") (pin "14") (pinfunction "PA4/SPI1_NSS/USART2_CK/ADC12_IN4_14") (pintype "bidirectional"))
    )
    (net (code "42") (name "Net-(UC1-PA5{slash}SPI1_SCK{slash}ADC12_IN5)") (class "Default")
      (node (ref "R6") (pin "2") (pinfunction "2_2") (pintype "passive"))
      (node (ref "UC1") (pin "15") (pinfunction "PA5/SPI1_SCK/ADC12_IN5_15") (pintype "bidirectional"))
    )
    (net (code "43") (name "Net-(UC1-PA6{slash}SPI1_MISO{slash}ADC12_IN6{slash}TIM3_CH1)") (class "Default")
      (node (ref "R7") (pin "2") (pinfunction "2_2") (pintype "passive"))
      (node (ref "UC1") (pin "16") (pinfunction "PA6/SPI1_MISO/ADC12_IN6/TIM3_CH1_16") (pintype "bidirectional"))
    )
    (net (code "44") (name "Net-(UC1-PA7{slash}SPI1_MOSI{slash}ADC12_IN7{slash}TIM3_CH2)") (class "Default")
      (node (ref "R8") (pin "2") (pinfunction "2_2") (pintype "passive"))
      (node (ref "UC1") (pin "17") (pinfunction "PA7/SPI1_MOSI/ADC12_IN7/TIM3_CH2_17") (pintype "bidirectional"))
    )
    (net (code "45") (name "Net-(UC1-PB0{slash}ADC12_IN8{slash}TIM3_CH3)") (class "Default")
      (node (ref "R23") (pin "2") (pinfunction "2_2") (pintype "passive"))
      (node (ref "UC1") (pin "18") (pinfunction "PB0/ADC12_IN8/TIM3_CH3_18") (pintype "bidirectional"))
    )
    (net (code "46") (name "Net-(UC1-PB1{slash}ADC12_IN9{slash}TIM3_CH4)") (class "Default")
      (node (ref "R10") (pin "2") (pinfunction "2_2") (pintype "passive"))
      (node (ref "UC1") (pin "19") (pinfunction "PB1/ADC12_IN9/TIM3_CH4_19") (pintype "bidirectional"))
    )
    (net (code "47") (name "Net-(UC1-PB10{slash}I2C2_SCL{slash}USART3_TX)") (class "Default")
      (node (ref "R2") (pin "2") (pinfunction "2_2") (pintype "passive"))
      (node (ref "UC1") (pin "21") (pinfunction "PB10/I2C2_SCL/USART3_TX_21") (pintype "input"))
    )
    (net (code "48") (name "Net-(UC1-PD0-OSC_IN)") (class "Default")
      (node (ref "C7") (pin "2") (pinfunction "2_2") (pintype "passive"))
      (node (ref "Q1") (pin "2") (pinfunction "2_2") (pintype "passive"))
      (node (ref "UC1") (pin "5") (pinfunction "PD0-OSC_IN_5") (pintype "input"))
    )
    (net (code "49") (name "Net-(UC1-PD1-OSC_OUT)") (class "Default")
      (node (ref "C6") (pin "2") (pinfunction "2_2") (pintype "passive"))
      (node (ref "Q1") (pin "1") (pinfunction "1_1") (pintype "passive"))
      (node (ref "UC1") (pin "6") (pinfunction "PD1-OSC_OUT_6") (pintype "input"))
    )
    (net (code "50") (name "POT_1") (class "Default")
      (node (ref "R1") (pin "P$2") (pinfunction "S_P$2") (pintype "passive"))
      (node (ref "UC1") (pin "13") (pinfunction "PA3/USART2_RX/ADC12_IN3/TIM2_CH4_13") (pintype "bidirectional"))
    )
    (net (code "51") (name "POT_2") (class "Default")
      (node (ref "R5") (pin "P$2") (pinfunction "S_P$2") (pintype "passive"))
      (node (ref "UC1") (pin "12") (pinfunction "PA2/USART2_TX/ADC12_IN2/TIM2_CH3_12") (pintype "bidirectional"))
    )
    (net (code "52") (name "POT_3") (class "Default")
      (node (ref "R11") (pin "P$2") (pinfunction "S_P$2") (pintype "passive"))
      (node (ref "UC1") (pin "11") (pinfunction "PA1/USART2_RTS/ADC12_IN1/TIM2_CH2_11") (pintype "bidirectional"))
    )
    (net (code "53") (name "POT_4") (class "Default")
      (node (ref "R21") (pin "P$2") (pinfunction "S_P$2") (pintype "passive"))
      (node (ref "UC1") (pin "10") (pinfunction "PA0_WKUP/USART2_CTS/ADC12_IN0/TIM2_CH1_ETR_10") (pintype "bidirectional"))
    )
    (net (code "54") (name "RESET") (class "Default")
      (node (ref "JP2") (pin "10") (pinfunction "10_10") (pintype "passive"))
      (node (ref "R3") (pin "1") (pinfunction "1_1") (pintype "passive"))
      (node (ref "SW3") (pin "B") (pinfunction "S_B") (pintype "passive"))
      (node (ref "SW3") (pin "B'") (pinfunction "S1_B'") (pintype "passive"))
      (node (ref "UC1") (pin "7") (pinfunction "NRST_7") (pintype "input"))
    )
    (net (code "55") (name "RX") (class "Default")
      (node (ref "JP1") (pin "4") (pinfunction "4_4") (pintype "passive"))
      (node (ref "UC1") (pin "31") (pinfunction "PA10/USART1_RX/TIM1_CH3_31") (pintype "bidirectional"))
    )
    (net (code "56") (name "SW_DUAL") (class "Default")
      (node (ref "SW2") (pin "3") (pinfunction "3_3") (pintype "passive"))
      (node (ref "SW2") (pin "4") (pinfunction "4_4") (pintype "passive"))
      (node (ref "UC1") (pin "3") (pinfunction "PC14-OSC32_IN_3") (pintype "input"))
    )
    (net (code "57") (name "SW_MODE") (class "Default")
      (node (ref "SW1") (pin "3") (pinfunction "3_3") (pintype "passive"))
      (node (ref "SW1") (pin "4") (pinfunction "4_4") (pintype "passive"))
      (node (ref "UC1") (pin "2") (pinfunction "PC13-TAMPER-RTC_2") (pintype "input"))
    )
    (net (code "58") (name "SW_TRIG_1") (class "Default")
      (node (ref "SW6") (pin "P2") (pinfunction "A2_P2") (pintype "passive"))
      (node (ref "SW6") (pin "P5") (pinfunction "B2_P5") (pintype "passive"))
      (node (ref "UC1") (pin "40") (pinfunction "PB4/NJTRST_40") (pintype "bidirectional"))
    )
    (net (code "59") (name "SW_TRIG_2") (class "Default")
      (node (ref "SW4") (pin "P2") (pinfunction "A2_P2") (pintype "passive"))
      (node (ref "SW4") (pin "P5") (pinfunction "B2_P5") (pintype "passive"))
      (node (ref "UC1") (pin "29") (pinfunction "PA8/USART1_CK/TIM1_CH1/MCO_29") (pintype "bidirectional"))
    )
    (net (code "60") (name "TRIG_1") (class "Default")
      (node (ref "Q3") (pin "C") (pinfunction "C_C") (pintype "passive"))
      (node (ref "R28") (pin "1") (pinfunction "1_1") (pintype "passive"))
      (node (ref "UC1") (pin "33") (pinfunction "PA12/USART1_RTS/CAN_TX/TIM1_ETR/USBDP_33") (pintype "bidirectional"))
    )
    (net (code "61") (name "TRIG_2") (class "Default")
      (node (ref "Q2") (pin "C") (pinfunction "C_C") (pintype "passive"))
      (node (ref "R16") (pin "1") (pinfunction "1_1") (pintype "passive"))
      (node (ref "UC1") (pin "22") (pinfunction "PB11/I2C2_SDA/USART3_RX_22") (pintype "input"))
    )
    (net (code "62") (name "TX") (class "Default")
      (node (ref "JP1") (pin "5") (pinfunction "5_5") (pintype "passive"))
      (node (ref "UC1") (pin "30") (pinfunction "PA9/USART1_TX/TIM1_CH2_30") (pintype "input"))
    )
    (net (code "63") (name "VCC") (class "Default")
      (node (ref "C16") (pin "1") (pinfunction "1_1") (pintype "passive"))
      (node (ref "C2") (pin "+") (pinfunction "+_+") (pintype "passive"))
      (node (ref "C21") (pin "1") (pinfunction "1_1") (pintype "passive"))
      (node (ref "D1") (pin "C") (pinfunction "C_C") (pintype "passive"))
      (node (ref "IC1") (pin "3") (pinfunction "VIN_3") (pintype "input"))
      (node (ref "IC4") (pin "8") (pinfunction "V+_8") (pintype "power_in"))
      (node (ref "IC5") (pin "8") (pinfunction "V+_8") (pintype "power_in"))
    )
    (net (code "64") (name "VEE") (class "Default")
      (node (ref "C1") (pin "-") (pinfunction "-_-") (pintype "passive"))
      (node (ref "C18") (pin "2") (pinfunction "2_2") (pintype "passive"))
      (node (ref "C24") (pin "2") (pinfunction "2_2") (pintype "passive"))
      (node (ref "D2") (pin "A") (pinfunction "A_A") (pintype "passive"))
      (node (ref "IC4") (pin "4") (pinfunction "V-_4") (pintype "power_in"))
      (node (ref "IC5") (pin "4") (pinfunction "V-_4") (pintype "power_in"))
      (node (ref "R25") (pin "1") (pinfunction "1_1") (pintype "passive"))
    )
    (net (code "65") (name "unconnected-(J3-2-PadP2)") (class "Default")
      (node (ref "J3") (pin "P2") (pinfunction "2_P2") (pintype "passive"))
    )
    (net (code "66") (name "unconnected-(J4-2-PadP2)") (class "Default")
      (node (ref "J4") (pin "P2") (pinfunction "2_P2") (pintype "passive"))
    )
    (net (code "67") (name "unconnected-(JP1-Pad2)") (class "Default")
      (node (ref "JP1") (pin "2") (pinfunction "2_2") (pintype "passive"))
    )
    (net (code "68") (name "unconnected-(JP1-Pad3)") (class "Default")
      (node (ref "JP1") (pin "3") (pinfunction "3_3") (pintype "passive"))
    )
    (net (code "69") (name "unconnected-(JP1-Pad6)") (class "Default")
      (node (ref "JP1") (pin "6") (pinfunction "6_6") (pintype "passive"))
    )
    (net (code "70") (name "unconnected-(JP2-Pad7)") (class "Default")
      (node (ref "JP2") (pin "7") (pinfunction "7_7") (pintype "passive"))
    )
    (net (code "71") (name "unconnected-(SW4A-A1-PadP1)") (class "Default")
      (node (ref "SW4") (pin "P1") (pinfunction "A1_P1") (pintype "passive"))
    )
    (net (code "72") (name "unconnected-(SW4A-B1-PadP4)") (class "Default")
      (node (ref "SW4") (pin "P4") (pinfunction "B1_P4") (pintype "passive"))
    )
    (net (code "73") (name "unconnected-(SW6A-A1-PadP1)") (class "Default")
      (node (ref "SW6") (pin "P1") (pinfunction "A1_P1") (pintype "passive"))
    )
    (net (code "74") (name "unconnected-(SW6A-B1-PadP4)") (class "Default")
      (node (ref "SW6") (pin "P4") (pinfunction "B1_P4") (pintype "passive"))
    )
    (net (code "75") (name "unconnected-(UC1-PA11{slash}USART1_CTS{slash}CAN_RX{slash}TIM1_CH4{slash}USBDM-Pad32)") (class "Default")
      (node (ref "UC1") (pin "32") (pinfunction "PA11/USART1_CTS/CAN_RX/TIM1_CH4/USBDM_32") (pintype "bidirectional"))
    )
    (net (code "76") (name "unconnected-(UC1-PB5{slash}I2C1_SMBA-Pad41)") (class "Default")
      (node (ref "UC1") (pin "41") (pinfunction "PB5/I2C1_SMBA_41") (pintype "input"))
    )
    (net (code "77") (name "unconnected-(UC1-PB6{slash}I2C1_SCL{slash}TIM4_CH1-Pad42)") (class "Default")
      (node (ref "UC1") (pin "42") (pinfunction "PB6/I2C1_SCL/TIM4_CH1_42") (pintype "input"))
    )
    (net (code "78") (name "unconnected-(UC1-PB7{slash}I2C1_SDA{slash}TIM4_CH2-Pad43)") (class "Default")
      (node (ref "UC1") (pin "43") (pinfunction "PB7/I2C1_SDA/TIM4_CH2_43") (pintype "bidirectional"))
    )
    (net (code "79") (name "unconnected-(UC1-PB8{slash}TIM4_CH3-Pad45)") (class "Default")
      (node (ref "UC1") (pin "45") (pinfunction "PB8/TIM4_CH3_45") (pintype "bidirectional"))
    )
    (net (code "80") (name "unconnected-(UC1-PB14{slash}SPI2_MISO{slash}USART3_RTS{slash}TIM1_CH2N-Pad27)") (class "Default")
      (node (ref "UC1") (pin "27") (pinfunction "PB14/SPI2_MISO/USART3_RTS/TIM1_CH2N_27") (pintype "input"))
    )
    (net (code "81") (name "unconnected-(UC1-PC15-OSC32_OUT-Pad4)") (class "Default")
      (node (ref "UC1") (pin "4") (pinfunction "PC15-OSC32_OUT_4") (pintype "input"))
    )
  )
)
